# Extension_connectors.net
KiCad netlist of a schematic drawn in Altium Designer
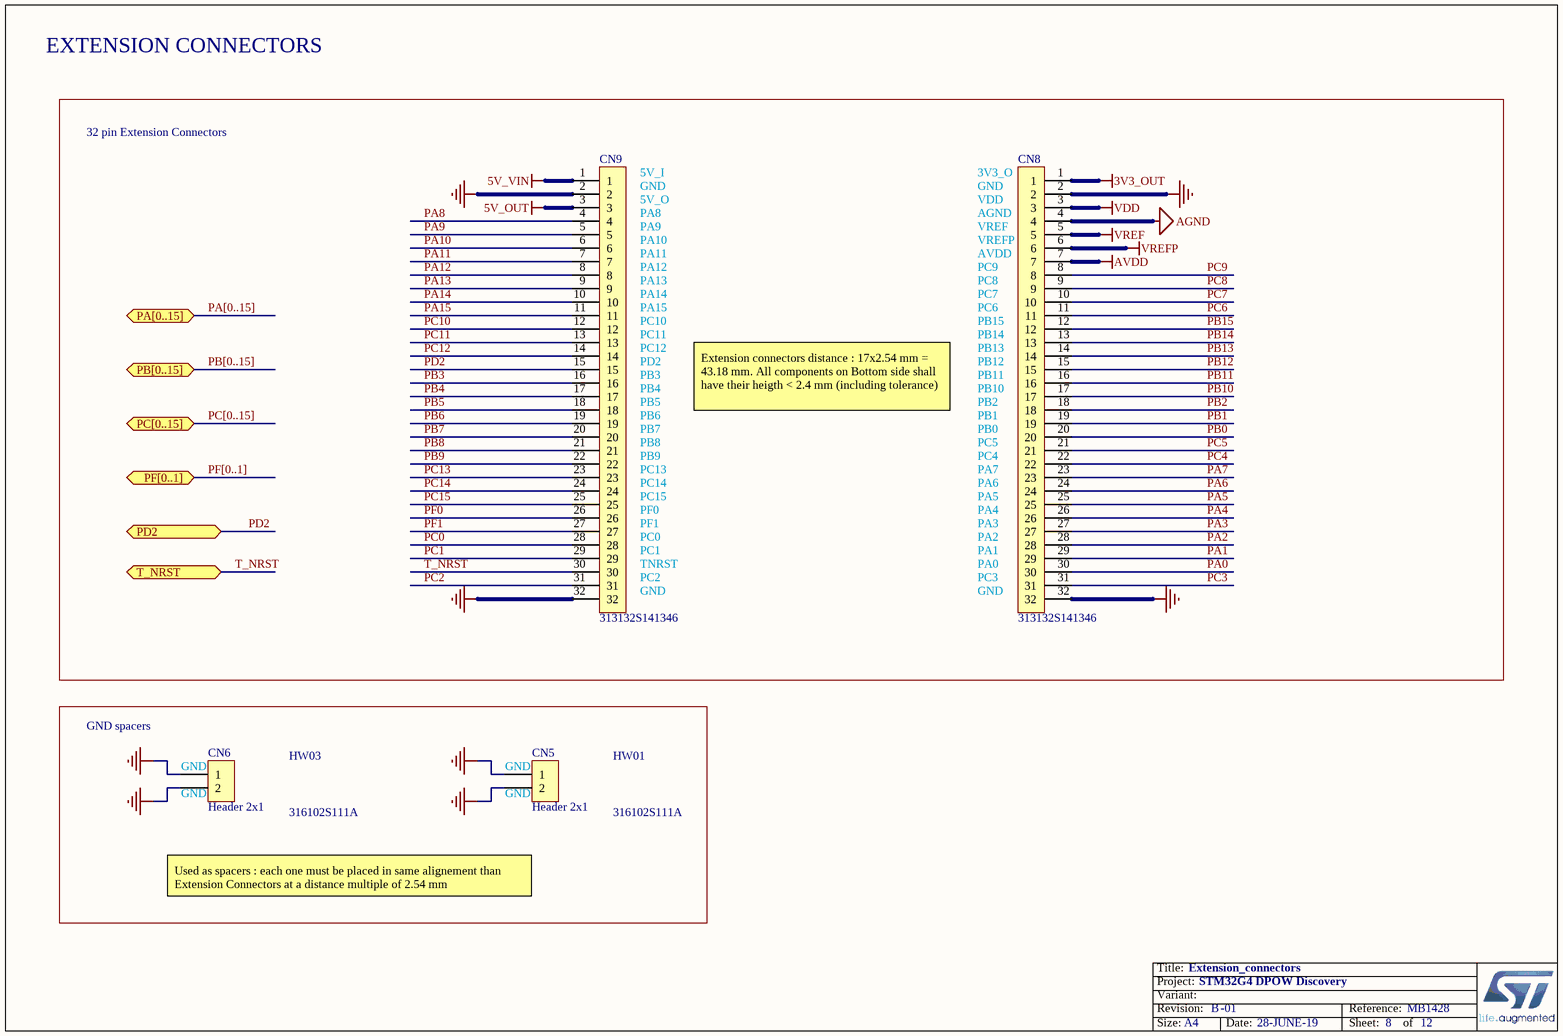
[diagram p0: Extension_connectors.SchDoc]

(export (version "E")
  (design (tool "Eeschema 10.0.6"))
  (components
    (comp (ref "CN5")
      (value "Header 2x1")
      (footprint "CON_LYCONN_313102S141346")
      (description "Header 2x1, 2.54mm, VR, TH, height 5.84mm/5.08 mm, height total 13.46 mm")
      (fields
        (field (name "INTERNAL_PART_NUMBER") "MCD-01668")
        (field (name "MANUFACTURER_PART_NUMBER") "313102S141346")
        (field (name "PROVIDED_BY") "SUBCO")
      )
      (libsource (lib "MCD_PARTS_database") (part "Header 2x1"))
    )
    (comp (ref "CN6")
      (value "Header 2x1")
      (footprint "CON_LYCONN_313102S141346")
      (description "Header 2x1, 2.54mm, VR, TH, height 5.84mm/5.08 mm, height total 13.46 mm")
      (fields
        (field (name "INTERNAL_PART_NUMBER") "MCD-01668")
        (field (name "MANUFACTURER_PART_NUMBER") "313102S141346")
        (field (name "PROVIDED_BY") "SUBCO")
      )
      (libsource (lib "MCD_PARTS_database") (part "Header 2x1"))
    )
    (comp (ref "CN8")
      (value "313132S141346")
      (footprint "CON_LYCONN_313132S141346")
      (description "'Header 32x1, 2.54mm, VR, TH, height 5.84mm/5.08 mm, height total 13.46 mm")
      (fields (field (name "INTERNAL_PART_NUMBER") "MCD-01728") (field (name "MANUFACTURER") "LYCONN"))
      (libsource (lib "") (part "Header 32x1_1"))
    )
    (comp (ref "CN9")
      (value "313132S141346")
      (footprint "CON_LYCONN_313132S141346")
      (description "'Header 32x1, 2.54mm, VR, TH, height 5.84mm/5.08 mm, height total 13.46 mm")
      (fields (field (name "INTERNAL_PART_NUMBER") "MCD-01728") (field (name "MANUFACTURER") "LYCONN"))
      (libsource (lib "MCD_PARTS_database") (part "Header 32x1"))
    )
    (comp (ref "HW01")
      (value "316102S111A")
      (description "Jumper, height 6mm, Black, 2.54mm, 3A, 20 mohm, open")
      (fields
        (field (name "INTERNAL_PART_NUMBER") "MCD-01849")
        (field (name "MANUFACTURER") "JIUBABA")
        (field (name "PROVIDED_BY") "SUBCO")
      )
      (libsource (lib "MCD_PARTS_database") (part "JUMPER_OPEN"))
    )
    (comp (ref "HW03")
      (value "316102S111A")
      (description "Jumper, height 6mm, Black, 2.54mm, 3A, 20 mohm, open")
      (fields
        (field (name "INTERNAL_PART_NUMBER") "MCD-01849")
        (field (name "MANUFACTURER") "JIUBABA")
        (field (name "PROVIDED_BY") "SUBCO")
      )
      (libsource (lib "MCD_PARTS_database") (part "JUMPER_OPEN"))
    )
  )
  (nets
    (net (code "1") (name "/PA0") (class "Default")
      (node (ref "CN8") (pin "30") (pinfunction "30_30") (pintype "passive"))
    )
    (net (code "2") (name "/PA1") (class "Default")
      (node (ref "CN8") (pin "29") (pinfunction "29_29") (pintype "passive"))
    )
    (net (code "3") (name "/PA2") (class "Default")
      (node (ref "CN8") (pin "28") (pinfunction "28_28") (pintype "passive"))
    )
    (net (code "4") (name "/PA3") (class "Default")
      (node (ref "CN8") (pin "27") (pinfunction "27_27") (pintype "passive"))
    )
    (net (code "5") (name "/PA4") (class "Default")
      (node (ref "CN8") (pin "26") (pinfunction "26_26") (pintype "passive"))
    )
    (net (code "6") (name "/PA5") (class "Default")
      (node (ref "CN8") (pin "25") (pinfunction "25_25") (pintype "passive"))
    )
    (net (code "7") (name "/PA6") (class "Default")
      (node (ref "CN8") (pin "24") (pinfunction "24_24") (pintype "passive"))
    )
    (net (code "8") (name "/PA7") (class "Default")
      (node (ref "CN8") (pin "23") (pinfunction "23_23") (pintype "passive"))
    )
    (net (code "9") (name "/PA8") (class "Default")
      (node (ref "CN9") (pin "4") (pinfunction "4_4") (pintype "passive"))
    )
    (net (code "10") (name "/PA9") (class "Default")
      (node (ref "CN9") (pin "5") (pinfunction "5_5") (pintype "passive"))
    )
    (net (code "11") (name "/PA10") (class "Default")
      (node (ref "CN9") (pin "6") (pinfunction "6_6") (pintype "passive"))
    )
    (net (code "12") (name "/PA11") (class "Default")
      (node (ref "CN9") (pin "7") (pinfunction "7_7") (pintype "passive"))
    )
    (net (code "13") (name "/PA12") (class "Default")
      (node (ref "CN9") (pin "8") (pinfunction "8_8") (pintype "passive"))
    )
    (net (code "14") (name "/PA13") (class "Default")
      (node (ref "CN9") (pin "9") (pinfunction "9_9") (pintype "passive"))
    )
    (net (code "15") (name "/PA14") (class "Default")
      (node (ref "CN9") (pin "10") (pinfunction "10_10") (pintype "passive"))
    )
    (net (code "16") (name "/PA15") (class "Default")
      (node (ref "CN9") (pin "11") (pinfunction "11_11") (pintype "passive"))
    )
    (net (code "18") (name "/PB0") (class "Default")
      (node (ref "CN8") (pin "20") (pinfunction "20_20") (pintype "passive"))
    )
    (net (code "19") (name "/PB1") (class "Default")
      (node (ref "CN8") (pin "19") (pinfunction "19_19") (pintype "passive"))
    )
    (net (code "20") (name "/PB2") (class "Default")
      (node (ref "CN8") (pin "18") (pinfunction "18_18") (pintype "passive"))
    )
    (net (code "21") (name "/PB3") (class "Default")
      (node (ref "CN9") (pin "16") (pinfunction "16_16") (pintype "passive"))
    )
    (net (code "22") (name "/PB4") (class "Default")
      (node (ref "CN9") (pin "17") (pinfunction "17_17") (pintype "passive"))
    )
    (net (code "23") (name "/PB5") (class "Default")
      (node (ref "CN9") (pin "18") (pinfunction "18_18") (pintype "passive"))
    )
    (net (code "24") (name "/PB6") (class "Default")
      (node (ref "CN9") (pin "19") (pinfunction "19_19") (pintype "passive"))
    )
    (net (code "25") (name "/PB7") (class "Default")
      (node (ref "CN9") (pin "20") (pinfunction "20_20") (pintype "passive"))
    )
    (net (code "26") (name "/PB8") (class "Default")
      (node (ref "CN9") (pin "21") (pinfunction "21_21") (pintype "passive"))
    )
    (net (code "27") (name "/PB9") (class "Default")
      (node (ref "CN9") (pin "22") (pinfunction "22_22") (pintype "passive"))
    )
    (net (code "28") (name "/PB10") (class "Default")
      (node (ref "CN8") (pin "17") (pinfunction "17_17") (pintype "passive"))
    )
    (net (code "29") (name "/PB11") (class "Default")
      (node (ref "CN8") (pin "16") (pinfunction "16_16") (pintype "passive"))
    )
    (net (code "30") (name "/PB12") (class "Default")
      (node (ref "CN8") (pin "15") (pinfunction "15_15") (pintype "passive"))
    )
    (net (code "31") (name "/PB13") (class "Default")
      (node (ref "CN8") (pin "14") (pinfunction "14_14") (pintype "passive"))
    )
    (net (code "32") (name "/PB14") (class "Default")
      (node (ref "CN8") (pin "13") (pinfunction "13_13") (pintype "passive"))
    )
    (net (code "33") (name "/PB15") (class "Default")
      (node (ref "CN8") (pin "12") (pinfunction "12_12") (pintype "passive"))
    )
    (net (code "35") (name "/PC0") (class "Default")
      (node (ref "CN9") (pin "28") (pinfunction "28_28") (pintype "passive"))
    )
    (net (code "36") (name "/PC1") (class "Default")
      (node (ref "CN9") (pin "29") (pinfunction "29_29") (pintype "passive"))
    )
    (net (code "37") (name "/PC2") (class "Default")
      (node (ref "CN9") (pin "31") (pinfunction "31_31") (pintype "passive"))
    )
    (net (code "38") (name "/PC3") (class "Default")
      (node (ref "CN8") (pin "31") (pinfunction "31_31") (pintype "passive"))
    )
    (net (code "39") (name "/PC4") (class "Default")
      (node (ref "CN8") (pin "22") (pinfunction "22_22") (pintype "passive"))
    )
    (net (code "40") (name "/PC5") (class "Default")
      (node (ref "CN8") (pin "21") (pinfunction "21_21") (pintype "passive"))
    )
    (net (code "41") (name "/PC6") (class "Default")
      (node (ref "CN8") (pin "11") (pinfunction "11_11") (pintype "passive"))
    )
    (net (code "42") (name "/PC7") (class "Default")
      (node (ref "CN8") (pin "10") (pinfunction "10_10") (pintype "passive"))
    )
    (net (code "43") (name "/PC8") (class "Default")
      (node (ref "CN8") (pin "9") (pinfunction "9_9") (pintype "passive"))
    )
    (net (code "44") (name "/PC9") (class "Default")
      (node (ref "CN8") (pin "8") (pinfunction "8_8") (pintype "passive"))
    )
    (net (code "45") (name "/PC10") (class "Default")
      (node (ref "CN9") (pin "12") (pinfunction "12_12") (pintype "passive"))
    )
    (net (code "46") (name "/PC11") (class "Default")
      (node (ref "CN9") (pin "13") (pinfunction "13_13") (pintype "passive"))
    )
    (net (code "47") (name "/PC12") (class "Default")
      (node (ref "CN9") (pin "14") (pinfunction "14_14") (pintype "passive"))
    )
    (net (code "48") (name "/PC13") (class "Default")
      (node (ref "CN9") (pin "23") (pinfunction "23_23") (pintype "passive"))
    )
    (net (code "49") (name "/PC14") (class "Default")
      (node (ref "CN9") (pin "24") (pinfunction "24_24") (pintype "passive"))
    )
    (net (code "50") (name "/PC15") (class "Default")
      (node (ref "CN9") (pin "25") (pinfunction "25_25") (pintype "passive"))
    )
    (net (code "52") (name "/PD2") (class "Default")
      (node (ref "CN9") (pin "15") (pinfunction "15_15") (pintype "passive"))
    )
    (net (code "53") (name "/PF0") (class "Default")
      (node (ref "CN9") (pin "26") (pinfunction "26_26") (pintype "passive"))
    )
    (net (code "54") (name "/PF1") (class "Default")
      (node (ref "CN9") (pin "27") (pinfunction "27_27") (pintype "passive"))
    )
    (net (code "56") (name "/T_NRST") (class "Default")
      (node (ref "CN9") (pin "30") (pinfunction "30_30") (pintype "passive"))
    )
    (net (code "57") (name "3V3_OUT") (class "Default")
      (node (ref "CN8") (pin "1") (pinfunction "1_1") (pintype "passive"))
    )
    (net (code "58") (name "5V_OUT") (class "Default")
      (node (ref "CN9") (pin "3") (pinfunction "3_3") (pintype "passive"))
    )
    (net (code "59") (name "5V_VIN") (class "Default")
      (node (ref "CN9") (pin "1") (pinfunction "1_1") (pintype "passive"))
    )
    (net (code "60") (name "AGND") (class "Default")
      (node (ref "CN8") (pin "4") (pinfunction "4_4") (pintype "passive"))
    )
    (net (code "61") (name "AVDD") (class "Default")
      (node (ref "CN8") (pin "7") (pinfunction "7_7") (pintype "passive"))
    )
    (net (code "62") (name "GND") (class "Default")
      (node (ref "CN5") (pin "1") (pinfunction "1_1") (pintype "passive"))
      (node (ref "CN5") (pin "2") (pinfunction "2_2") (pintype "passive"))
      (node (ref "CN6") (pin "1") (pinfunction "1_1") (pintype "passive"))
      (node (ref "CN6") (pin "2") (pinfunction "2_2") (pintype "passive"))
      (node (ref "CN8") (pin "2") (pinfunction "2_2") (pintype "passive"))
      (node (ref "CN8") (pin "32") (pinfunction "32_32") (pintype "passive"))
      (node (ref "CN9") (pin "2") (pinfunction "2_2") (pintype "passive"))
      (node (ref "CN9") (pin "32") (pinfunction "32_32") (pintype "passive"))
    )
    (net (code "63") (name "VDD") (class "Default")
      (node (ref "CN8") (pin "3") (pinfunction "3_3") (pintype "passive"))
    )
    (net (code "64") (name "VREF") (class "Default")
      (node (ref "CN8") (pin "5") (pinfunction "5_5") (pintype "passive"))
    )
    (net (code "65") (name "VREFP") (class "Default")
      (node (ref "CN8") (pin "6") (pinfunction "6_6") (pintype "passive"))
    )
  )
)
